# LatarMain.net
KiCad netlist of a schematic drawn in EAGLE
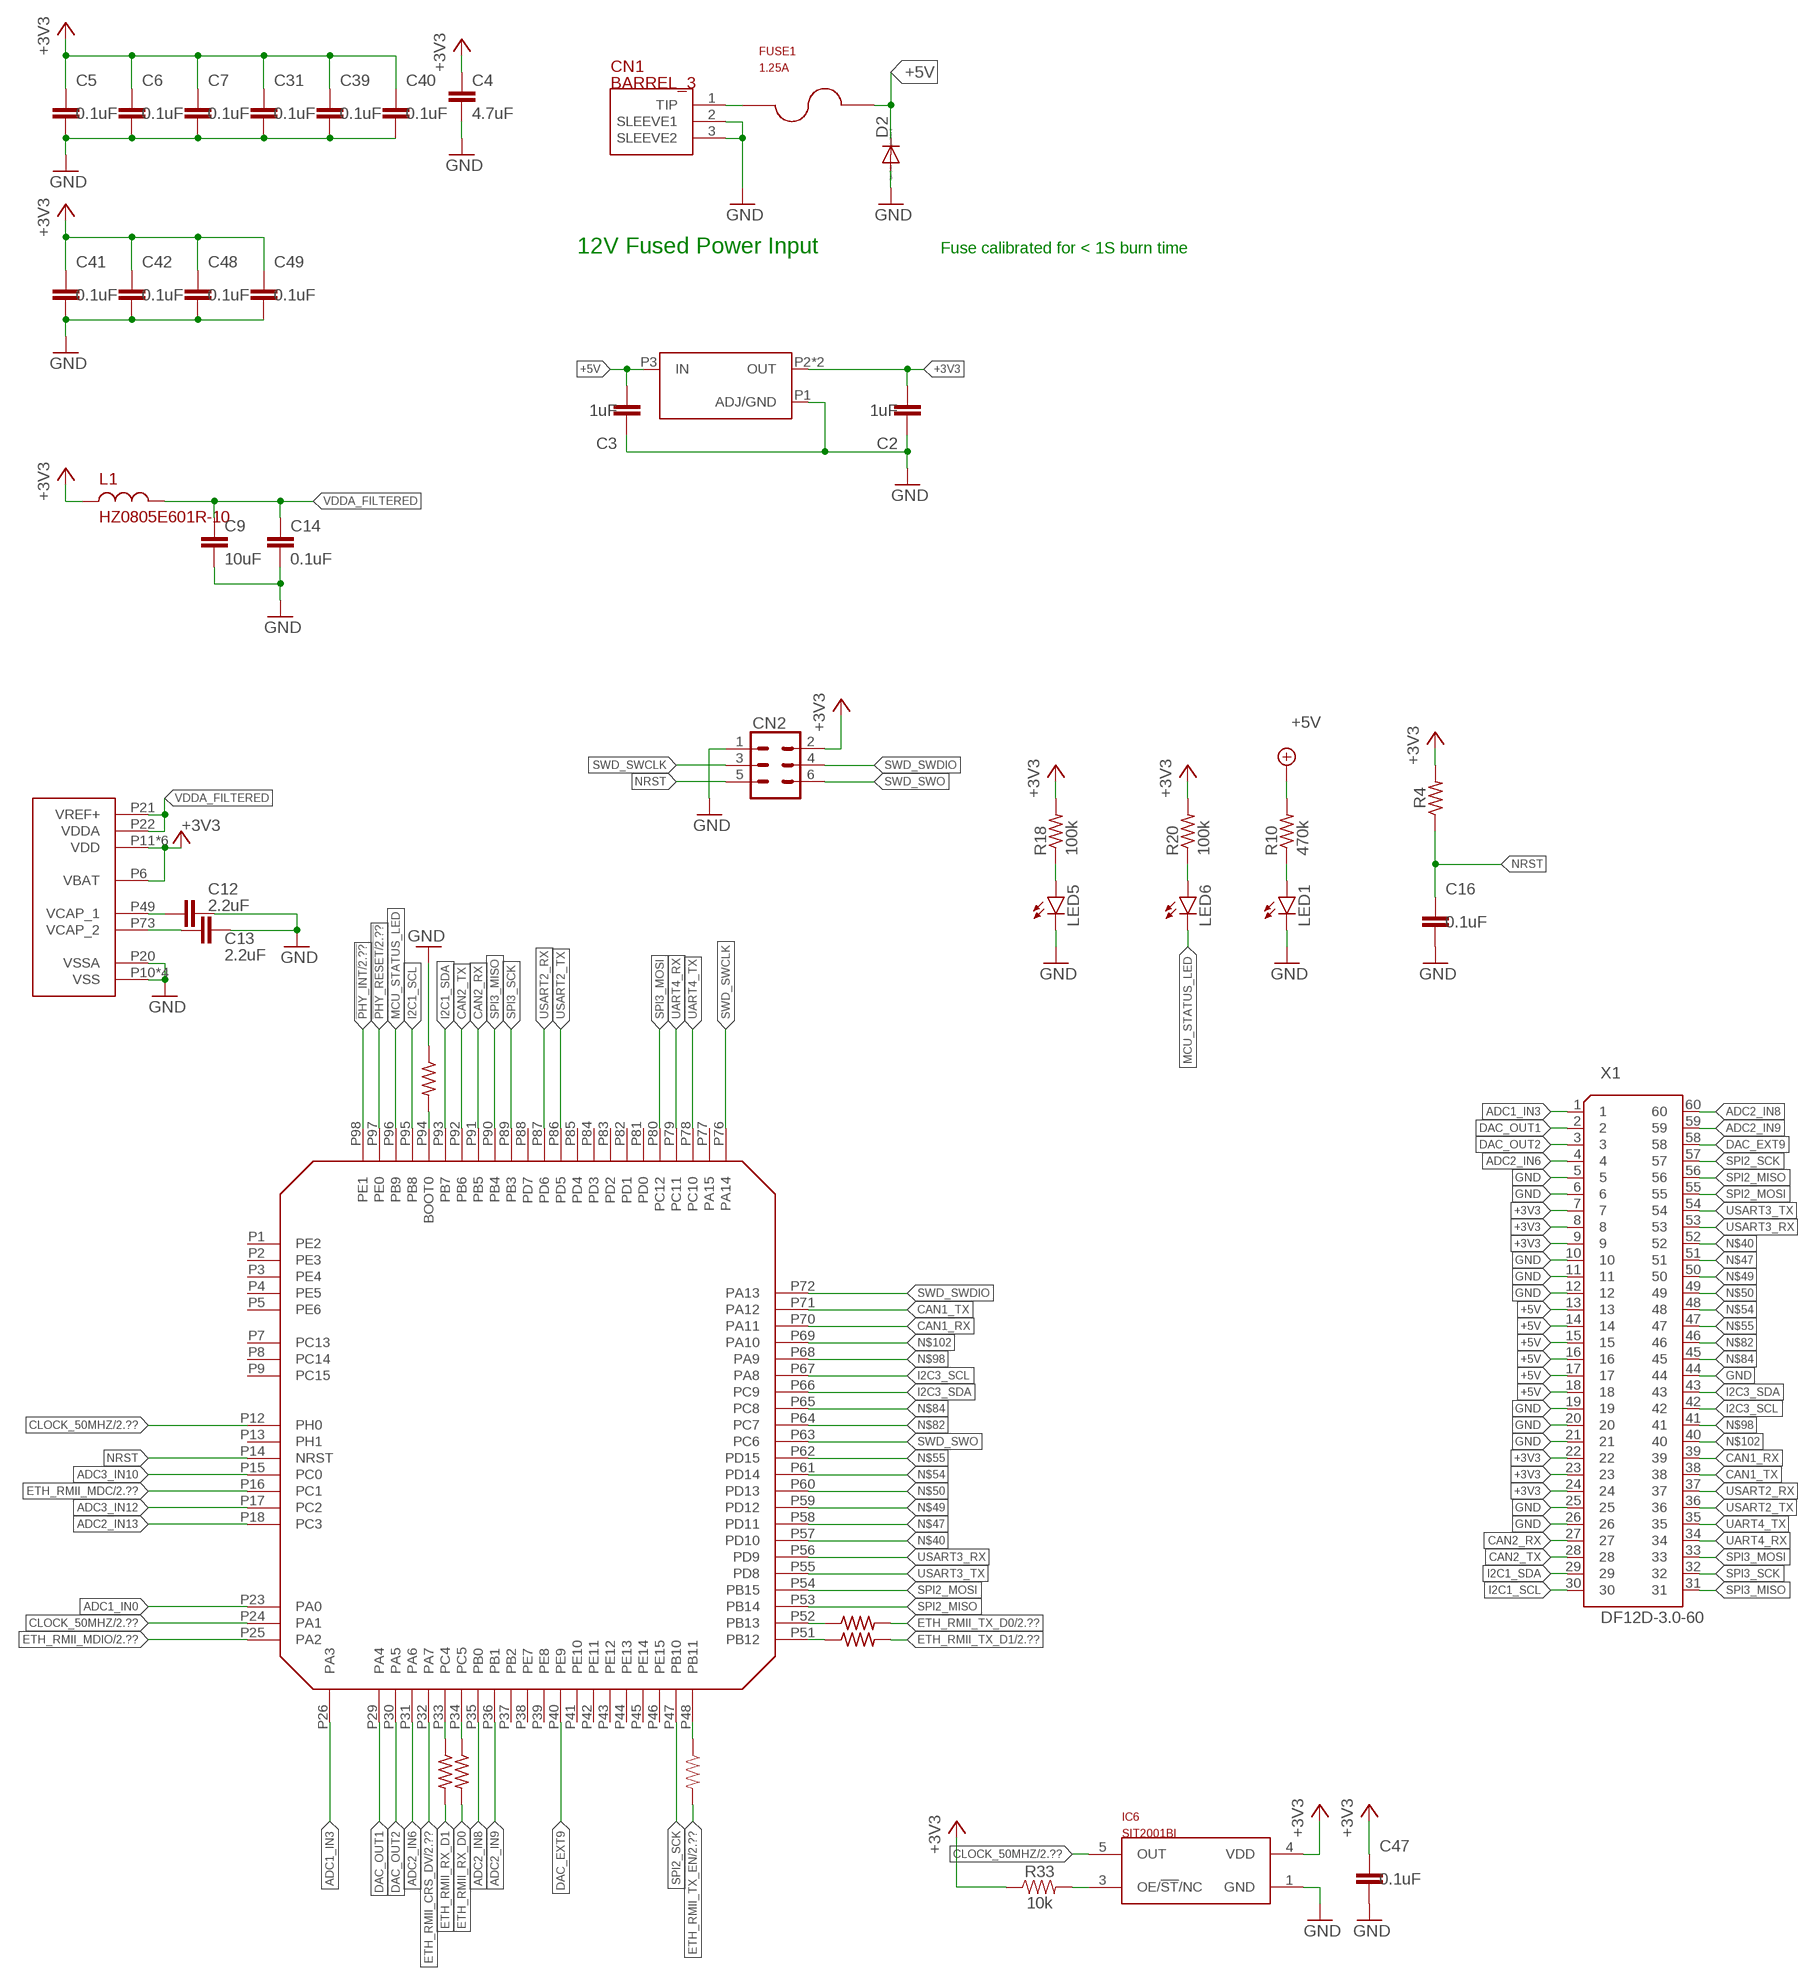
[diagram p0: schematic, sheet 1]
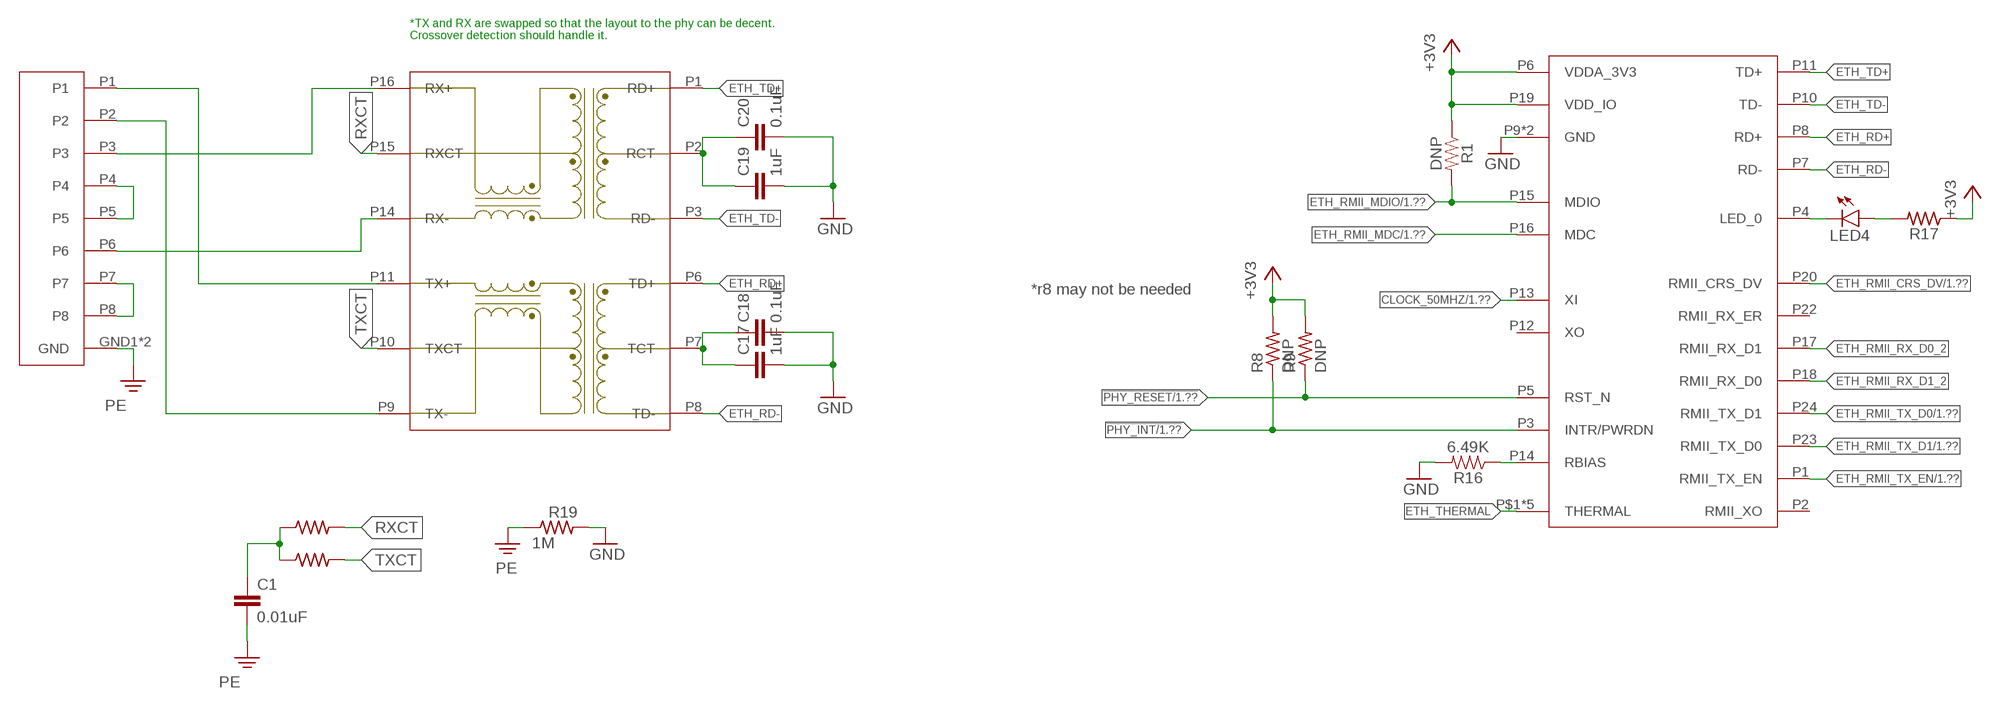
[diagram p1: schematic, sheet 2]

(export (version "E")
  (design (tool "Eeschema 10.0.6"))
  (components
    (comp (ref "C1")
      (value "0.01uF")
      (footprint "eagle-import:C0805")
      (libsource (lib "eagle-import") (part "C-EUC0805"))
    )
    (comp (ref "C17")
      (value "1uF")
      (footprint "eagle-import:C0805")
      (libsource (lib "eagle-import") (part "C-EUC0805"))
    )
    (comp (ref "C18")
      (value "0.1uF")
      (footprint "eagle-import:C0805")
      (libsource (lib "eagle-import") (part "C-EUC0805"))
    )
    (comp (ref "C19")
      (value "1uF")
      (footprint "eagle-import:C0805")
      (libsource (lib "eagle-import") (part "C-EUC0805"))
    )
    (comp (ref "C20")
      (value "0.1uF")
      (footprint "eagle-import:C0805")
      (libsource (lib "eagle-import") (part "C-EUC0805"))
    )
    (comp (ref "LED4")
      (value "LEDCHIP-LED0603")
      (footprint "eagle-import:CHIP-LED0603")
      (libsource (lib "eagle-import") (part "LEDCHIP-LED0603"))
    )
    (comp (ref "R1")
      (value "DNP")
      (footprint "eagle-import:0603")
      (libsource (lib "eagle-import") (part "RESISTOR0603"))
    )
    (comp (ref "R2")
      (value "75R")
      (footprint "eagle-import:R0805")
      (libsource (lib "eagle-import") (part "R-US_R0805"))
    )
    (comp (ref "R5")
      (value "75R")
      (footprint "eagle-import:R0805")
      (libsource (lib "eagle-import") (part "R-US_R0805"))
    )
    (comp (ref "R8")
      (value "DNP")
      (footprint "eagle-import:R0603")
      (libsource (lib "eagle-import") (part "R-US_R0603"))
    )
    (comp (ref "R9")
      (value "DNP")
      (footprint "eagle-import:R0603")
      (libsource (lib "eagle-import") (part "R-US_R0603"))
    )
    (comp (ref "R16")
      (value "6.49K")
      (footprint "eagle-import:0603")
      (libsource (lib "eagle-import") (part "RESISTOR0603"))
    )
    (comp (ref "R17")
      (value "100k")
      (footprint "eagle-import:R0603")
      (libsource (lib "eagle-import") (part "R-US_R0603"))
    )
    (comp (ref "R19")
      (value "1M")
      (footprint "eagle-import:R1206")
      (libsource (lib "eagle-import") (part "R-US_R1206"))
    )
    (comp (ref "U$15")
      (value "749013011")
      (footprint "eagle-import:749013011")
      (libsource (lib "eagle-import") (part "749013011"))
    )
    (comp (ref "U$16")
      (value "A120645-ND")
      (footprint "eagle-import:A120645-ND")
      (libsource (lib "eagle-import") (part "A120645-ND"))
    )
    (comp (ref "U$17")
      (value "DP83825I")
      (footprint "eagle-import:DP83825I")
      (libsource (lib "eagle-import") (part "DP83825I"))
    )
    (comp (ref "C2")
      (value "1uF")
      (footprint "eagle-import:C1206")
      (libsource (lib "eagle-import") (part "C-EUC1206"))
    )
    (comp (ref "C3")
      (value "1uF")
      (footprint "eagle-import:C1206")
      (libsource (lib "eagle-import") (part "C-EUC1206"))
    )
    (comp (ref "C4")
      (value "4.7uF")
      (footprint "eagle-import:C0805")
      (libsource (lib "eagle-import") (part "C-EUC0805"))
    )
    (comp (ref "C5")
      (value "0.1uF")
      (footprint "eagle-import:C0603")
      (libsource (lib "eagle-import") (part "C-EUC0603"))
    )
    (comp (ref "C6")
      (value "0.1uF")
      (footprint "eagle-import:C0603")
      (libsource (lib "eagle-import") (part "C-EUC0603"))
    )
    (comp (ref "C7")
      (value "0.1uF")
      (footprint "eagle-import:C0603")
      (libsource (lib "eagle-import") (part "C-EUC0603"))
    )
    (comp (ref "C9")
      (value "10uF")
      (footprint "eagle-import:C0805")
      (libsource (lib "eagle-import") (part "C-EUC0805"))
    )
    (comp (ref "C12")
      (value "2.2uF")
      (footprint "eagle-import:C0805")
      (libsource (lib "eagle-import") (part "C-EUC0805"))
    )
    (comp (ref "C13")
      (value "2.2uF")
      (footprint "eagle-import:C0805")
      (libsource (lib "eagle-import") (part "C-EUC0805"))
    )
    (comp (ref "C14")
      (value "0.1uF")
      (footprint "eagle-import:C0805")
      (libsource (lib "eagle-import") (part "C-EUC0805"))
    )
    (comp (ref "C16")
      (value "0.1uF")
      (footprint "eagle-import:C0603")
      (libsource (lib "eagle-import") (part "C-EUC0603"))
    )
    (comp (ref "C31")
      (value "0.1uF")
      (footprint "eagle-import:C0603")
      (libsource (lib "eagle-import") (part "C-EUC0603"))
    )
    (comp (ref "C39")
      (value "0.1uF")
      (footprint "eagle-import:C0603")
      (libsource (lib "eagle-import") (part "C-EUC0603"))
    )
    (comp (ref "C40")
      (value "0.1uF")
      (footprint "eagle-import:C0603")
      (libsource (lib "eagle-import") (part "C-EUC0603"))
    )
    (comp (ref "C41")
      (value "0.1uF")
      (footprint "eagle-import:C0603")
      (libsource (lib "eagle-import") (part "C-EUC0603"))
    )
    (comp (ref "C42")
      (value "0.1uF")
      (footprint "eagle-import:C0603")
      (libsource (lib "eagle-import") (part "C-EUC0603"))
    )
    (comp (ref "C47")
      (value "0.1uF")
      (footprint "eagle-import:C0603")
      (libsource (lib "eagle-import") (part "C-EUC0603"))
    )
    (comp (ref "C48")
      (value "0.1uF")
      (footprint "eagle-import:C0603")
      (libsource (lib "eagle-import") (part "C-EUC0603"))
    )
    (comp (ref "C49")
      (value "0.1uF")
      (footprint "eagle-import:C0603")
      (libsource (lib "eagle-import") (part "C-EUC0603"))
    )
    (comp (ref "CN1")
      (value "BARREL_3")
      (footprint "eagle-import:PJ-002AH")
      (libsource (lib "eagle-import") (part "BARREL_3"))
    )
    (comp (ref "CN2")
      (value "CONN_03X22X3_SILK_MALE_PTH")
      (footprint "eagle-import:2X3")
      (libsource (lib "eagle-import") (part "CONN_03X22X3_SILK_MALE_PTH"))
    )
    (comp (ref "D2")
      (value "DIODE-DO214AC")
      (footprint "eagle-import:DO214AC")
      (libsource (lib "eagle-import") (part "DIODE-DO214AC"))
    )
    (comp (ref "FUSE1")
      (value "1.25A")
      (footprint "eagle-import:BEL_FUSE_2SMD")
      (libsource (lib "eagle-import") (part "FUSE"))
    )
    (comp (ref "IC6")
      (value "SIT2001BI")
      (footprint "eagle-import:SOT23-5")
      (libsource (lib "eagle-import") (part "SIT2001BI"))
    )
    (comp (ref "L1")
      (value "HZ0805E601R-10")
      (footprint "eagle-import:R0805")
      (libsource (lib "eagle-import") (part "HZ0805E601R-10"))
    )
    (comp (ref "LED1")
      (value "LEDCHIPLED_0603")
      (footprint "eagle-import:CHIPLED_0603")
      (libsource (lib "eagle-import") (part "LEDCHIPLED_0603"))
    )
    (comp (ref "LED5")
      (value "LEDCHIPLED_0603")
      (footprint "eagle-import:CHIPLED_0603")
      (libsource (lib "eagle-import") (part "LEDCHIPLED_0603"))
    )
    (comp (ref "LED6")
      (value "LEDCHIPLED_0603")
      (footprint "eagle-import:CHIPLED_0603")
      (libsource (lib "eagle-import") (part "LEDCHIPLED_0603"))
    )
    (comp (ref "R4")
      (value "10k")
      (footprint "eagle-import:R0805")
      (libsource (lib "eagle-import") (part "R-US_R0805"))
    )
    (comp (ref "R10")
      (value "470k")
      (footprint "eagle-import:R0603")
      (libsource (lib "eagle-import") (part "R-US_R0603"))
    )
    (comp (ref "R18")
      (value "100k")
      (footprint "eagle-import:R0603")
      (libsource (lib "eagle-import") (part "R-US_R0603"))
    )
    (comp (ref "R20")
      (value "100k")
      (footprint "eagle-import:R0603")
      (libsource (lib "eagle-import") (part "R-US_R0603"))
    )
    (comp (ref "R32")
      (value "50k")
      (footprint "eagle-import:R0402")
      (libsource (lib "eagle-import") (part "R-US_R0402"))
    )
    (comp (ref "R33")
      (value "10k")
      (footprint "eagle-import:0805")
      (libsource (lib "eagle-import") (part "RESISTOR0805"))
    )
    (comp (ref "R34")
      (value "10k")
      (footprint "eagle-import:R0805")
      (libsource (lib "eagle-import") (part "R-US_R0805"))
    )
    (comp (ref "R39")
      (value "50k")
      (footprint "eagle-import:R0402")
      (libsource (lib "eagle-import") (part "R-US_R0402"))
    )
    (comp (ref "R40")
      (value "50k")
      (footprint "eagle-import:R0402")
      (libsource (lib "eagle-import") (part "R-US_R0402"))
    )
    (comp (ref "R41")
      (value "50k")
      (footprint "eagle-import:R0402")
      (libsource (lib "eagle-import") (part "R-US_R0402"))
    )
    (comp (ref "R42")
      (value "50k")
      (footprint "eagle-import:0603")
      (libsource (lib "eagle-import") (part "RESISTOR0603"))
    )
    (comp (ref "U$1")
      (value "AZ1117E")
      (footprint "eagle-import:SOT-223")
      (libsource (lib "eagle-import") (part "AZ1117E"))
    )
    (comp (ref "U$2")
      (value "STM32_F407_LQFP100")
      (footprint "eagle-import:STM32_LQFP100")
      (libsource (lib "eagle-import") (part "STM32_F407_LQFP100"))
    )
    (comp (ref "X1")
      (value "DF12D-3.0-60")
      (footprint "eagle-import:DF12-3.0-60")
      (libsource (lib "eagle-import") (part "DF12D-3.0-60"))
    )
  )
  (nets
    (net (code "1") (name "+3V3") (class "Default")
      (node (ref "C2") (pin "2") (pinfunction "2_2") (pintype "passive"))
      (node (ref "C31") (pin "1") (pinfunction "1_1") (pintype "passive"))
      (node (ref "C39") (pin "1") (pinfunction "1_1") (pintype "passive"))
      (node (ref "C4") (pin "1") (pinfunction "1_1") (pintype "passive"))
      (node (ref "C40") (pin "1") (pinfunction "1_1") (pintype "passive"))
      (node (ref "C41") (pin "1") (pinfunction "1_1") (pintype "passive"))
      (node (ref "C42") (pin "1") (pinfunction "1_1") (pintype "passive"))
      (node (ref "C47") (pin "1") (pinfunction "1_1") (pintype "passive"))
      (node (ref "C48") (pin "1") (pinfunction "1_1") (pintype "passive"))
      (node (ref "C49") (pin "1") (pinfunction "1_1") (pintype "passive"))
      (node (ref "C5") (pin "1") (pinfunction "1_1") (pintype "passive"))
      (node (ref "C6") (pin "1") (pinfunction "1_1") (pintype "passive"))
      (node (ref "C7") (pin "1") (pinfunction "1_1") (pintype "passive"))
      (node (ref "CN2") (pin "2") (pinfunction "2_2") (pintype "bidirectional"))
      (node (ref "IC6") (pin "4") (pinfunction "VDD_4") (pintype "bidirectional"))
      (node (ref "L1") (pin "1") (pinfunction "1_1") (pintype "passive"))
      (node (ref "R1") (pin "1") (pinfunction "1_1") (pintype "passive"))
      (node (ref "R17") (pin "1") (pinfunction "1_1") (pintype "passive"))
      (node (ref "R18") (pin "2") (pinfunction "2_2") (pintype "passive"))
      (node (ref "R20") (pin "2") (pinfunction "2_2") (pintype "passive"))
      (node (ref "R33") (pin "1") (pinfunction "1_1") (pintype "passive"))
      (node (ref "R4") (pin "2") (pinfunction "2_2") (pintype "passive"))
      (node (ref "R8") (pin "2") (pinfunction "2_2") (pintype "passive"))
      (node (ref "R9") (pin "2") (pinfunction "2_2") (pintype "passive"))
      (node (ref "U$1") (pin "P2") (pinfunction "OUT_P2") (pintype "bidirectional"))
      (node (ref "U$1") (pin "TAB") (pinfunction "OUT_TAB") (pintype "bidirectional"))
      (node (ref "U$17") (pin "P19") (pinfunction "VDD_IO_P19") (pintype "bidirectional"))
      (node (ref "U$17") (pin "P6") (pinfunction "VDDA_3V3_P6") (pintype "bidirectional"))
      (node (ref "U$2") (pin "P100") (pinfunction "VDD_P100") (pintype "bidirectional"))
      (node (ref "U$2") (pin "P11") (pinfunction "VDD_P11") (pintype "bidirectional"))
      (node (ref "U$2") (pin "P19") (pinfunction "VDD_P19") (pintype "bidirectional"))
      (node (ref "U$2") (pin "P28") (pinfunction "VDD_P28") (pintype "bidirectional"))
      (node (ref "U$2") (pin "P50") (pinfunction "VDD_P50") (pintype "bidirectional"))
      (node (ref "U$2") (pin "P6") (pinfunction "VBAT_P6") (pintype "bidirectional"))
      (node (ref "U$2") (pin "P75") (pinfunction "VDD_P75") (pintype "bidirectional"))
      (node (ref "X1") (pin "22") (pinfunction "22_22") (pintype "bidirectional"))
      (node (ref "X1") (pin "23") (pinfunction "23_23") (pintype "bidirectional"))
      (node (ref "X1") (pin "24") (pinfunction "24_24") (pintype "bidirectional"))
      (node (ref "X1") (pin "7") (pinfunction "7_7") (pintype "bidirectional"))
      (node (ref "X1") (pin "8") (pinfunction "8_8") (pintype "bidirectional"))
      (node (ref "X1") (pin "9") (pinfunction "9_9") (pintype "bidirectional"))
    )
    (net (code "2") (name "+5V") (class "Default")
      (node (ref "C3") (pin "2") (pinfunction "2_2") (pintype "passive"))
      (node (ref "D2") (pin "C") (pinfunction "C_C") (pintype "passive"))
      (node (ref "FUSE1") (pin "2") (pinfunction "2_2") (pintype "power_in"))
      (node (ref "R10") (pin "2") (pinfunction "2_2") (pintype "passive"))
      (node (ref "U$1") (pin "P3") (pinfunction "IN_P3") (pintype "bidirectional"))
      (node (ref "X1") (pin "13") (pinfunction "13_13") (pintype "bidirectional"))
      (node (ref "X1") (pin "14") (pinfunction "14_14") (pintype "bidirectional"))
      (node (ref "X1") (pin "15") (pinfunction "15_15") (pintype "bidirectional"))
      (node (ref "X1") (pin "16") (pinfunction "16_16") (pintype "bidirectional"))
      (node (ref "X1") (pin "17") (pinfunction "17_17") (pintype "bidirectional"))
      (node (ref "X1") (pin "18") (pinfunction "18_18") (pintype "bidirectional"))
    )
    (net (code "3") (name "ADC1_IN0") (class "Default")
      (node (ref "U$2") (pin "P23") (pinfunction "PA0_P23") (pintype "bidirectional"))
    )
    (net (code "4") (name "ADC1_IN3") (class "Default")
      (node (ref "U$2") (pin "P26") (pinfunction "PA3_P26") (pintype "bidirectional"))
      (node (ref "X1") (pin "1") (pinfunction "1_1") (pintype "bidirectional"))
    )
    (net (code "5") (name "ADC2_IN6") (class "Default")
      (node (ref "U$2") (pin "P31") (pinfunction "PA6_P31") (pintype "bidirectional"))
      (node (ref "X1") (pin "4") (pinfunction "4_4") (pintype "bidirectional"))
    )
    (net (code "6") (name "ADC2_IN8") (class "Default")
      (node (ref "U$2") (pin "P35") (pinfunction "PB0_P35") (pintype "bidirectional"))
      (node (ref "X1") (pin "60") (pinfunction "60_60") (pintype "bidirectional"))
    )
    (net (code "7") (name "ADC2_IN9") (class "Default")
      (node (ref "U$2") (pin "P36") (pinfunction "PB1_P36") (pintype "bidirectional"))
      (node (ref "X1") (pin "59") (pinfunction "59_59") (pintype "bidirectional"))
    )
    (net (code "8") (name "ADC2_IN13") (class "Default")
      (node (ref "U$2") (pin "P18") (pinfunction "PC3_P18") (pintype "bidirectional"))
    )
    (net (code "9") (name "ADC3_IN10") (class "Default")
      (node (ref "U$2") (pin "P15") (pinfunction "PC0_P15") (pintype "bidirectional"))
    )
    (net (code "10") (name "ADC3_IN12") (class "Default")
      (node (ref "U$2") (pin "P17") (pinfunction "PC2_P17") (pintype "bidirectional"))
    )
    (net (code "11") (name "CAN1_RX") (class "Default")
      (node (ref "U$2") (pin "P70") (pinfunction "PA11_P70") (pintype "bidirectional"))
      (node (ref "X1") (pin "39") (pinfunction "39_39") (pintype "bidirectional"))
    )
    (net (code "12") (name "CAN1_TX") (class "Default")
      (node (ref "U$2") (pin "P71") (pinfunction "PA12_P71") (pintype "bidirectional"))
      (node (ref "X1") (pin "38") (pinfunction "38_38") (pintype "bidirectional"))
    )
    (net (code "13") (name "CAN2_RX") (class "Default")
      (node (ref "U$2") (pin "P91") (pinfunction "PB5_P91") (pintype "bidirectional"))
      (node (ref "X1") (pin "27") (pinfunction "27_27") (pintype "bidirectional"))
    )
    (net (code "14") (name "CAN2_TX") (class "Default")
      (node (ref "U$2") (pin "P92") (pinfunction "PB6_P92") (pintype "bidirectional"))
      (node (ref "X1") (pin "28") (pinfunction "28_28") (pintype "bidirectional"))
    )
    (net (code "15") (name "CLOCK_50MHZ") (class "Default")
      (node (ref "IC6") (pin "5") (pinfunction "OUT_5") (pintype "bidirectional"))
      (node (ref "U$17") (pin "P13") (pinfunction "XI_P13") (pintype "bidirectional"))
      (node (ref "U$2") (pin "P12") (pinfunction "PH0_P12") (pintype "bidirectional"))
      (node (ref "U$2") (pin "P24") (pinfunction "PA1_P24") (pintype "bidirectional"))
    )
    (net (code "16") (name "DAC_EXT9") (class "Default")
      (node (ref "U$2") (pin "P40") (pinfunction "PE9_P40") (pintype "bidirectional"))
      (node (ref "X1") (pin "58") (pinfunction "58_58") (pintype "bidirectional"))
    )
    (net (code "17") (name "DAC_OUT1") (class "Default")
      (node (ref "U$2") (pin "P29") (pinfunction "PA4_P29") (pintype "bidirectional"))
      (node (ref "X1") (pin "2") (pinfunction "2_2") (pintype "bidirectional"))
    )
    (net (code "18") (name "DAC_OUT2") (class "Default")
      (node (ref "U$2") (pin "P30") (pinfunction "PA5_P30") (pintype "bidirectional"))
      (node (ref "X1") (pin "3") (pinfunction "3_3") (pintype "bidirectional"))
    )
    (net (code "19") (name "ETH_RD+") (class "Default")
      (node (ref "U$15") (pin "P6") (pinfunction "TD+_P6") (pintype "bidirectional"))
      (node (ref "U$17") (pin "P8") (pinfunction "RD+_P8") (pintype "bidirectional"))
    )
    (net (code "20") (name "ETH_RD-") (class "Default")
      (node (ref "U$15") (pin "P8") (pinfunction "TD-_P8") (pintype "bidirectional"))
      (node (ref "U$17") (pin "P7") (pinfunction "RD-_P7") (pintype "bidirectional"))
    )
    (net (code "21") (name "ETH_RMII_CRS_DV") (class "Default")
      (node (ref "U$17") (pin "P20") (pinfunction "RMII_CRS_DV_P20") (pintype "bidirectional"))
      (node (ref "U$2") (pin "P32") (pinfunction "PA7_P32") (pintype "bidirectional"))
    )
    (net (code "22") (name "ETH_RMII_MDC") (class "Default")
      (node (ref "U$17") (pin "P16") (pinfunction "MDC_P16") (pintype "bidirectional"))
      (node (ref "U$2") (pin "P16") (pinfunction "PC1_P16") (pintype "bidirectional"))
    )
    (net (code "23") (name "ETH_RMII_MDIO") (class "Default")
      (node (ref "R1") (pin "2") (pinfunction "2_2") (pintype "passive"))
      (node (ref "U$17") (pin "P15") (pinfunction "MDIO_P15") (pintype "bidirectional"))
      (node (ref "U$2") (pin "P25") (pinfunction "PA2_P25") (pintype "bidirectional"))
    )
    (net (code "24") (name "ETH_RMII_RX_D0") (class "Default")
      (node (ref "R32") (pin "2") (pinfunction "2_2") (pintype "passive"))
    )
    (net (code "25") (name "ETH_RMII_RX_D0_2") (class "Default")
      (node (ref "U$17") (pin "P17") (pinfunction "RMII_RX_D1_P17") (pintype "bidirectional"))
    )
    (net (code "26") (name "ETH_RMII_RX_D1") (class "Default")
      (node (ref "R39") (pin "2") (pinfunction "2_2") (pintype "passive"))
    )
    (net (code "27") (name "ETH_RMII_RX_D1_2") (class "Default")
      (node (ref "U$17") (pin "P18") (pinfunction "RMII_RX_D0_P18") (pintype "bidirectional"))
    )
    (net (code "28") (name "ETH_RMII_TX_D0") (class "Default")
      (node (ref "R40") (pin "2") (pinfunction "2_2") (pintype "passive"))
      (node (ref "U$17") (pin "P24") (pinfunction "RMII_TX_D1_P24") (pintype "bidirectional"))
    )
    (net (code "29") (name "ETH_RMII_TX_D1") (class "Default")
      (node (ref "R41") (pin "2") (pinfunction "2_2") (pintype "passive"))
      (node (ref "U$17") (pin "P23") (pinfunction "RMII_TX_D0_P23") (pintype "bidirectional"))
    )
    (net (code "30") (name "ETH_RMII_TX_EN") (class "Default")
      (node (ref "R42") (pin "2") (pinfunction "2_2") (pintype "passive"))
      (node (ref "U$17") (pin "P1") (pinfunction "RMII_TX_EN_P1") (pintype "bidirectional"))
    )
    (net (code "31") (name "ETH_TD+") (class "Default")
      (node (ref "U$15") (pin "P1") (pinfunction "RD+_P1") (pintype "bidirectional"))
      (node (ref "U$17") (pin "P11") (pinfunction "TD+_P11") (pintype "bidirectional"))
    )
    (net (code "32") (name "ETH_TD-") (class "Default")
      (node (ref "U$15") (pin "P3") (pinfunction "RD-_P3") (pintype "bidirectional"))
      (node (ref "U$17") (pin "P10") (pinfunction "TD-_P10") (pintype "bidirectional"))
    )
    (net (code "33") (name "ETH_THERMAL") (class "Default")
      (node (ref "U$17") (pin "P$1") (pinfunction "THERMAL_P$1") (pintype "bidirectional"))
      (node (ref "U$17") (pin "P$2") (pinfunction "THERMAL_P$2") (pintype "bidirectional"))
      (node (ref "U$17") (pin "P$3") (pinfunction "THERMAL_P$3") (pintype "bidirectional"))
      (node (ref "U$17") (pin "P$4") (pinfunction "THERMAL_P$4") (pintype "bidirectional"))
      (node (ref "U$17") (pin "PT") (pinfunction "THERMAL_PT") (pintype "bidirectional"))
    )
    (net (code "34") (name "GND") (class "Default")
      (node (ref "C12") (pin "2") (pinfunction "2_2") (pintype "passive"))
      (node (ref "C13") (pin "2") (pinfunction "2_2") (pintype "passive"))
      (node (ref "C14") (pin "2") (pinfunction "2_2") (pintype "passive"))
      (node (ref "C16") (pin "2") (pinfunction "2_2") (pintype "passive"))
      (node (ref "C17") (pin "2") (pinfunction "2_2") (pintype "passive"))
      (node (ref "C18") (pin "2") (pinfunction "2_2") (pintype "passive"))
      (node (ref "C19") (pin "2") (pinfunction "2_2") (pintype "passive"))
      (node (ref "C2") (pin "1") (pinfunction "1_1") (pintype "passive"))
      (node (ref "C20") (pin "2") (pinfunction "2_2") (pintype "passive"))
      (node (ref "C3") (pin "1") (pinfunction "1_1") (pintype "passive"))
      (node (ref "C31") (pin "2") (pinfunction "2_2") (pintype "passive"))
      (node (ref "C39") (pin "2") (pinfunction "2_2") (pintype "passive"))
      (node (ref "C4") (pin "2") (pinfunction "2_2") (pintype "passive"))
      (node (ref "C40") (pin "2") (pinfunction "2_2") (pintype "passive"))
      (node (ref "C41") (pin "2") (pinfunction "2_2") (pintype "passive"))
      (node (ref "C42") (pin "2") (pinfunction "2_2") (pintype "passive"))
      (node (ref "C47") (pin "2") (pinfunction "2_2") (pintype "passive"))
      (node (ref "C48") (pin "2") (pinfunction "2_2") (pintype "passive"))
      (node (ref "C49") (pin "2") (pinfunction "2_2") (pintype "passive"))
      (node (ref "C5") (pin "2") (pinfunction "2_2") (pintype "passive"))
      (node (ref "C6") (pin "2") (pinfunction "2_2") (pintype "passive"))
      (node (ref "C7") (pin "2") (pinfunction "2_2") (pintype "passive"))
      (node (ref "C9") (pin "2") (pinfunction "2_2") (pintype "passive"))
      (node (ref "CN1") (pin "2") (pinfunction "SLEEVE1_2") (pintype "bidirectional"))
      (node (ref "CN1") (pin "3") (pinfunction "SLEEVE2_3") (pintype "bidirectional"))
      (node (ref "CN2") (pin "1") (pinfunction "1_1") (pintype "bidirectional"))
      (node (ref "D2") (pin "A") (pinfunction "A_A") (pintype "passive"))
      (node (ref "IC6") (pin "1") (pinfunction "GND_1") (pintype "bidirectional"))
      (node (ref "LED1") (pin "C") (pinfunction "C_C") (pintype "passive"))
      (node (ref "LED5") (pin "C") (pinfunction "C_C") (pintype "passive"))
      (node (ref "R16") (pin "2") (pinfunction "2_2") (pintype "passive"))
      (node (ref "R19") (pin "2") (pinfunction "2_2") (pintype "passive"))
      (node (ref "R34") (pin "1") (pinfunction "1_1") (pintype "passive"))
      (node (ref "U$1") (pin "P1") (pinfunction "ADJ/GND_P1") (pintype "bidirectional"))
      (node (ref "U$17") (pin "P21") (pinfunction "GND_P21") (pintype "bidirectional"))
      (node (ref "U$17") (pin "P9") (pinfunction "GND_P9") (pintype "bidirectional"))
      (node (ref "U$2") (pin "P10") (pinfunction "VSS_P10") (pintype "bidirectional"))
      (node (ref "U$2") (pin "P20") (pinfunction "VSSA_P20") (pintype "bidirectional"))
      (node (ref "U$2") (pin "P27") (pinfunction "VSS_P27") (pintype "bidirectional"))
      (node (ref "U$2") (pin "P74") (pinfunction "VSS_P74") (pintype "bidirectional"))
      (node (ref "U$2") (pin "P99") (pinfunction "VSS_P99") (pintype "bidirectional"))
      (node (ref "X1") (pin "10") (pinfunction "10_10") (pintype "bidirectional"))
      (node (ref "X1") (pin "11") (pinfunction "11_11") (pintype "bidirectional"))
      (node (ref "X1") (pin "12") (pinfunction "12_12") (pintype "bidirectional"))
      (node (ref "X1") (pin "19") (pinfunction "19_19") (pintype "bidirectional"))
      (node (ref "X1") (pin "20") (pinfunction "20_20") (pintype "bidirectional"))
      (node (ref "X1") (pin "21") (pinfunction "21_21") (pintype "bidirectional"))
      (node (ref "X1") (pin "25") (pinfunction "25_25") (pintype "bidirectional"))
      (node (ref "X1") (pin "26") (pinfunction "26_26") (pintype "bidirectional"))
      (node (ref "X1") (pin "44") (pinfunction "44_44") (pintype "bidirectional"))
      (node (ref "X1") (pin "5") (pinfunction "5_5") (pintype "bidirectional"))
      (node (ref "X1") (pin "6") (pinfunction "6_6") (pintype "bidirectional"))
    )
    (net (code "35") (name "I2C1_SCL") (class "Default")
      (node (ref "U$2") (pin "P95") (pinfunction "PB8_P95") (pintype "bidirectional"))
      (node (ref "X1") (pin "30") (pinfunction "30_30") (pintype "bidirectional"))
    )
    (net (code "36") (name "I2C1_SDA") (class "Default")
      (node (ref "U$2") (pin "P93") (pinfunction "PB7_P93") (pintype "bidirectional"))
      (node (ref "X1") (pin "29") (pinfunction "29_29") (pintype "bidirectional"))
    )
    (net (code "37") (name "I2C3_SCL") (class "Default")
      (node (ref "U$2") (pin "P67") (pinfunction "PA8_P67") (pintype "bidirectional"))
      (node (ref "X1") (pin "42") (pinfunction "42_42") (pintype "bidirectional"))
    )
    (net (code "38") (name "I2C3_SDA") (class "Default")
      (node (ref "U$2") (pin "P66") (pinfunction "PC9_P66") (pintype "bidirectional"))
      (node (ref "X1") (pin "43") (pinfunction "43_43") (pintype "bidirectional"))
    )
    (net (code "39") (name "MCU_STATUS_LED") (class "Default")
      (node (ref "LED6") (pin "C") (pinfunction "C_C") (pintype "passive"))
      (node (ref "U$2") (pin "P96") (pinfunction "PB9_P96") (pintype "bidirectional"))
    )
    (net (code "40") (name "N$40") (class "Default")
      (node (ref "U$2") (pin "P57") (pinfunction "PD10_P57") (pintype "bidirectional"))
      (node (ref "X1") (pin "52") (pinfunction "52_52") (pintype "bidirectional"))
    )
    (net (code "41") (name "N$47") (class "Default")
      (node (ref "U$2") (pin "P58") (pinfunction "PD11_P58") (pintype "bidirectional"))
      (node (ref "X1") (pin "51") (pinfunction "51_51") (pintype "bidirectional"))
    )
    (net (code "42") (name "N$49") (class "Default")
      (node (ref "U$2") (pin "P59") (pinfunction "PD12_P59") (pintype "bidirectional"))
      (node (ref "X1") (pin "50") (pinfunction "50_50") (pintype "bidirectional"))
    )
    (net (code "43") (name "N$50") (class "Default")
      (node (ref "U$2") (pin "P60") (pinfunction "PD13_P60") (pintype "bidirectional"))
      (node (ref "X1") (pin "49") (pinfunction "49_49") (pintype "bidirectional"))
    )
    (net (code "44") (name "N$54") (class "Default")
      (node (ref "U$2") (pin "P61") (pinfunction "PD14_P61") (pintype "bidirectional"))
      (node (ref "X1") (pin "48") (pinfunction "48_48") (pintype "bidirectional"))
    )
    (net (code "45") (name "N$55") (class "Default")
      (node (ref "U$2") (pin "P62") (pinfunction "PD15_P62") (pintype "bidirectional"))
      (node (ref "X1") (pin "47") (pinfunction "47_47") (pintype "bidirectional"))
    )
    (net (code "46") (name "N$82") (class "Default")
      (node (ref "U$2") (pin "P64") (pinfunction "PC7_P64") (pintype "bidirectional"))
      (node (ref "X1") (pin "46") (pinfunction "46_46") (pintype "bidirectional"))
    )
    (net (code "47") (name "N$84") (class "Default")
      (node (ref "U$2") (pin "P65") (pinfunction "PC8_P65") (pintype "bidirectional"))
      (node (ref "X1") (pin "45") (pinfunction "45_45") (pintype "bidirectional"))
    )
    (net (code "48") (name "N$98") (class "Default")
      (node (ref "U$2") (pin "P68") (pinfunction "PA9_P68") (pintype "bidirectional"))
      (node (ref "X1") (pin "41") (pinfunction "41_41") (pintype "bidirectional"))
    )
    (net (code "49") (name "N$102") (class "Default")
      (node (ref "U$2") (pin "P69") (pinfunction "PA10_P69") (pintype "bidirectional"))
      (node (ref "X1") (pin "40") (pinfunction "40_40") (pintype "bidirectional"))
    )
    (net (code "50") (name "NRST") (class "Default")
      (node (ref "C16") (pin "1") (pinfunction "1_1") (pintype "passive"))
      (node (ref "CN2") (pin "5") (pinfunction "5_5") (pintype "bidirectional"))
      (node (ref "R4") (pin "1") (pinfunction "1_1") (pintype "passive"))
      (node (ref "U$2") (pin "P14") (pinfunction "NRST_P14") (pintype "bidirectional"))
    )
    (net (code "51") (name "Net-(C1-Pad1)") (class "Default")
      (node (ref "C1") (pin "1") (pinfunction "1_1") (pintype "passive"))
      (node (ref "R2") (pin "1") (pinfunction "1_1") (pintype "passive"))
      (node (ref "R5") (pin "1") (pinfunction "1_1") (pintype "passive"))
    )
    (net (code "52") (name "Net-(CN1-TIP)") (class "Default")
      (node (ref "CN1") (pin "1") (pinfunction "TIP_1") (pintype "bidirectional"))
      (node (ref "FUSE1") (pin "1") (pinfunction "1_1") (pintype "power_in"))
    )
    (net (code "53") (name "Net-(IC6-OE{slash}~{ST}{slash}NC)") (class "Default")
      (node (ref "IC6") (pin "3") (pinfunction "OE/~{ST}/NC_3") (pintype "bidirectional"))
      (node (ref "R33") (pin "2") (pinfunction "2_2") (pintype "passive"))
    )
    (net (code "54") (name "Net-(LED1-PadA)") (class "Default")
      (node (ref "LED1") (pin "A") (pinfunction "A_A") (pintype "passive"))
      (node (ref "R10") (pin "1") (pinfunction "1_1") (pintype "passive"))
    )
    (net (code "55") (name "Net-(LED4-PadA)") (class "Default")
      (node (ref "LED4") (pin "A") (pinfunction "A_A") (pintype "passive"))
      (node (ref "R17") (pin "2") (pinfunction "2_2") (pintype "passive"))
    )
    (net (code "56") (name "Net-(LED5-PadA)") (class "Default")
      (node (ref "LED5") (pin "A") (pinfunction "A_A") (pintype "passive"))
      (node (ref "R18") (pin "1") (pinfunction "1_1") (pintype "passive"))
    )
    (net (code "57") (name "Net-(LED6-PadA)") (class "Default")
      (node (ref "LED6") (pin "A") (pinfunction "A_A") (pintype "passive"))
      (node (ref "R20") (pin "1") (pinfunction "1_1") (pintype "passive"))
    )
    (net (code "58") (name "Net-(U$2-BOOT0)") (class "Default")
      (node (ref "R34") (pin "2") (pinfunction "2_2") (pintype "passive"))
      (node (ref "U$2") (pin "P94") (pinfunction "BOOT0_P94") (pintype "bidirectional"))
    )
    (net (code "59") (name "Net-(U$2-PB11)") (class "Default")
      (node (ref "R42") (pin "1") (pinfunction "1_1") (pintype "passive"))
      (node (ref "U$2") (pin "P48") (pinfunction "PB11_P48") (pintype "bidirectional"))
    )
    (net (code "60") (name "Net-(U$2-PB12)") (class "Default")
      (node (ref "R41") (pin "1") (pinfunction "1_1") (pintype "passive"))
      (node (ref "U$2") (pin "P51") (pinfunction "PB12_P51") (pintype "bidirectional"))
    )
    (net (code "61") (name "Net-(U$2-PB13)") (class "Default")
      (node (ref "R40") (pin "1") (pinfunction "1_1") (pintype "passive"))
      (node (ref "U$2") (pin "P52") (pinfunction "PB13_P52") (pintype "bidirectional"))
    )
    (net (code "62") (name "Net-(U$2-PC4)") (class "Default")
      (node (ref "R39") (pin "1") (pinfunction "1_1") (pintype "passive"))
      (node (ref "U$2") (pin "P33") (pinfunction "PC4_P33") (pintype "bidirectional"))
    )
    (net (code "63") (name "Net-(U$2-PC5)") (class "Default")
      (node (ref "R32") (pin "1") (pinfunction "1_1") (pintype "passive"))
      (node (ref "U$2") (pin "P34") (pinfunction "PC5_P34") (pintype "bidirectional"))
    )
    (net (code "64") (name "Net-(U$2-VCAP_1)") (class "Default")
      (node (ref "C12") (pin "1") (pinfunction "1_1") (pintype "passive"))
      (node (ref "U$2") (pin "P49") (pinfunction "VCAP_1_P49") (pintype "bidirectional"))
    )
    (net (code "65") (name "Net-(U$2-VCAP_2)") (class "Default")
      (node (ref "C13") (pin "1") (pinfunction "1_1") (pintype "passive"))
      (node (ref "U$2") (pin "P73") (pinfunction "VCAP_2_P73") (pintype "bidirectional"))
    )
    (net (code "66") (name "Net-(U$15-RCT)") (class "Default")
      (node (ref "C19") (pin "1") (pinfunction "1_1") (pintype "passive"))
      (node (ref "C20") (pin "1") (pinfunction "1_1") (pintype "passive"))
      (node (ref "U$15") (pin "P2") (pinfunction "RCT_P2") (pintype "bidirectional"))
    )
    (net (code "67") (name "Net-(U$15-RX+)") (class "Default")
      (node (ref "U$15") (pin "P16") (pinfunction "RX+_P16") (pintype "bidirectional"))
      (node (ref "U$16") (pin "P3") (pinfunction "P3_P3") (pintype "bidirectional"))
    )
    (net (code "68") (name "Net-(U$15-RX-)") (class "Default")
      (node (ref "U$15") (pin "P14") (pinfunction "RX-_P14") (pintype "bidirectional"))
      (node (ref "U$16") (pin "P6") (pinfunction "P6_P6") (pintype "bidirectional"))
    )
    (net (code "69") (name "Net-(U$15-TCT)") (class "Default")
      (node (ref "C17") (pin "1") (pinfunction "1_1") (pintype "passive"))
      (node (ref "C18") (pin "1") (pinfunction "1_1") (pintype "passive"))
      (node (ref "U$15") (pin "P7") (pinfunction "TCT_P7") (pintype "bidirectional"))
    )
    (net (code "70") (name "Net-(U$15-TX+)") (class "Default")
      (node (ref "U$15") (pin "P11") (pinfunction "TX+_P11") (pintype "bidirectional"))
      (node (ref "U$16") (pin "P1") (pinfunction "P1_P1") (pintype "bidirectional"))
    )
    (net (code "71") (name "Net-(U$15-TX-)") (class "Default")
      (node (ref "U$15") (pin "P9") (pinfunction "TX-_P9") (pintype "bidirectional"))
      (node (ref "U$16") (pin "P2") (pinfunction "P2_P2") (pintype "bidirectional"))
    )
    (net (code "72") (name "Net-(U$16-PadP4)") (class "Default")
      (node (ref "U$16") (pin "P4") (pinfunction "P4_P4") (pintype "bidirectional"))
      (node (ref "U$16") (pin "P5") (pinfunction "P5_P5") (pintype "bidirectional"))
    )
    (net (code "73") (name "Net-(U$16-PadP7)") (class "Default")
      (node (ref "U$16") (pin "P7") (pinfunction "P7_P7") (pintype "bidirectional"))
      (node (ref "U$16") (pin "P8") (pinfunction "P8_P8") (pintype "bidirectional"))
    )
    (net (code "74") (name "Net-(U$17-LED_0)") (class "Default")
      (node (ref "LED4") (pin "C") (pinfunction "C_C") (pintype "passive"))
      (node (ref "U$17") (pin "P4") (pinfunction "LED_0_P4") (pintype "bidirectional"))
    )
    (net (code "75") (name "Net-(U$17-RBIAS)") (class "Default")
      (node (ref "R16") (pin "1") (pinfunction "1_1") (pintype "passive"))
      (node (ref "U$17") (pin "P14") (pinfunction "RBIAS_P14") (pintype "bidirectional"))
    )
    (net (code "76") (name "PE") (class "Default")
      (node (ref "C1") (pin "2") (pinfunction "2_2") (pintype "passive"))
      (node (ref "R19") (pin "1") (pinfunction "1_1") (pintype "passive"))
      (node (ref "U$16") (pin "GND1") (pinfunction "GND_GND1") (pintype "bidirectional"))
      (node (ref "U$16") (pin "GND2") (pinfunction "GND_GND2") (pintype "bidirectional"))
    )
    (net (code "77") (name "RXCT") (class "Default")
      (node (ref "R2") (pin "2") (pinfunction "2_2") (pintype "passive"))
      (node (ref "U$15") (pin "P15") (pinfunction "RXCT_P15") (pintype "bidirectional"))
    )
    (net (code "78") (name "SPI2_MISO") (class "Default")
      (node (ref "U$2") (pin "P53") (pinfunction "PB14_P53") (pintype "bidirectional"))
      (node (ref "X1") (pin "56") (pinfunction "56_56") (pintype "bidirectional"))
    )
    (net (code "79") (name "SPI2_MOSI") (class "Default")
      (node (ref "U$2") (pin "P54") (pinfunction "PB15_P54") (pintype "bidirectional"))
      (node (ref "X1") (pin "55") (pinfunction "55_55") (pintype "bidirectional"))
    )
    (net (code "80") (name "SPI2_SCK") (class "Default")
      (node (ref "U$2") (pin "P47") (pinfunction "PB10_P47") (pintype "bidirectional"))
      (node (ref "X1") (pin "57") (pinfunction "57_57") (pintype "bidirectional"))
    )
    (net (code "81") (name "SPI3_MISO") (class "Default")
      (node (ref "U$2") (pin "P90") (pinfunction "PB4_P90") (pintype "bidirectional"))
      (node (ref "X1") (pin "31") (pinfunction "31_31") (pintype "bidirectional"))
    )
    (net (code "82") (name "SPI3_MOSI") (class "Default")
      (node (ref "U$2") (pin "P80") (pinfunction "PC12_P80") (pintype "bidirectional"))
      (node (ref "X1") (pin "33") (pinfunction "33_33") (pintype "bidirectional"))
    )
    (net (code "83") (name "SPI3_SCK") (class "Default")
      (node (ref "U$2") (pin "P89") (pinfunction "PB3_P89") (pintype "bidirectional"))
      (node (ref "X1") (pin "32") (pinfunction "32_32") (pintype "bidirectional"))
    )
    (net (code "84") (name "SWD_SWCLK") (class "Default")
      (node (ref "CN2") (pin "3") (pinfunction "3_3") (pintype "bidirectional"))
      (node (ref "U$2") (pin "P76") (pinfunction "PA14_P76") (pintype "bidirectional"))
    )
    (net (code "85") (name "SWD_SWDIO") (class "Default")
      (node (ref "CN2") (pin "4") (pinfunction "4_4") (pintype "bidirectional"))
      (node (ref "U$2") (pin "P72") (pinfunction "PA13_P72") (pintype "bidirectional"))
    )
    (net (code "86") (name "SWD_SWO") (class "Default")
      (node (ref "CN2") (pin "6") (pinfunction "6_6") (pintype "bidirectional"))
      (node (ref "U$2") (pin "P63") (pinfunction "PC6_P63") (pintype "bidirectional"))
    )
    (net (code "87") (name "TXCT") (class "Default")
      (node (ref "R5") (pin "2") (pinfunction "2_2") (pintype "passive"))
      (node (ref "U$15") (pin "P10") (pinfunction "TXCT_P10") (pintype "bidirectional"))
    )
    (net (code "88") (name "UART4_RX") (class "Default")
      (node (ref "U$2") (pin "P79") (pinfunction "PC11_P79") (pintype "bidirectional"))
      (node (ref "X1") (pin "34") (pinfunction "34_34") (pintype "bidirectional"))
    )
    (net (code "89") (name "UART4_TX") (class "Default")
      (node (ref "U$2") (pin "P78") (pinfunction "PC10_P78") (pintype "bidirectional"))
      (node (ref "X1") (pin "35") (pinfunction "35_35") (pintype "bidirectional"))
    )
    (net (code "90") (name "USART2_RX") (class "Default")
      (node (ref "U$2") (pin "P87") (pinfunction "PD6_P87") (pintype "bidirectional"))
      (node (ref "X1") (pin "37") (pinfunction "37_37") (pintype "bidirectional"))
    )
    (net (code "91") (name "USART2_TX") (class "Default")
      (node (ref "U$2") (pin "P86") (pinfunction "PD5_P86") (pintype "bidirectional"))
      (node (ref "X1") (pin "36") (pinfunction "36_36") (pintype "bidirectional"))
    )
    (net (code "92") (name "USART3_RX") (class "Default")
      (node (ref "U$2") (pin "P56") (pinfunction "PD9_P56") (pintype "bidirectional"))
      (node (ref "X1") (pin "53") (pinfunction "53_53") (pintype "bidirectional"))
    )
    (net (code "93") (name "USART3_TX") (class "Default")
      (node (ref "U$2") (pin "P55") (pinfunction "PD8_P55") (pintype "bidirectional"))
      (node (ref "X1") (pin "54") (pinfunction "54_54") (pintype "bidirectional"))
    )
    (net (code "94") (name "VDDA_FILTERED") (class "Default")
      (node (ref "C14") (pin "1") (pinfunction "1_1") (pintype "passive"))
      (node (ref "C9") (pin "1") (pinfunction "1_1") (pintype "passive"))
      (node (ref "L1") (pin "2") (pinfunction "2_2") (pintype "passive"))
      (node (ref "U$2") (pin "P21") (pinfunction "VREF+_P21") (pintype "bidirectional"))
      (node (ref "U$2") (pin "P22") (pinfunction "VDDA_P22") (pintype "bidirectional"))
    )
    (net (code "95") (name "unconnected-(U$2-PA15-PadP77)") (class "Default")
      (node (ref "U$2") (pin "P77") (pinfunction "PA15_P77") (pintype "bidirectional"))
    )
    (net (code "96") (name "unconnected-(U$2-PB2-PadP37)") (class "Default")
      (node (ref "U$2") (pin "P37") (pinfunction "PB2_P37") (pintype "bidirectional"))
    )
    (net (code "97") (name "unconnected-(U$2-PC13-PadP7)") (class "Default")
      (node (ref "U$2") (pin "P7") (pinfunction "PC13_P7") (pintype "bidirectional"))
    )
    (net (code "98") (name "unconnected-(U$2-PC14-PadP8)") (class "Default")
      (node (ref "U$2") (pin "P8") (pinfunction "PC14_P8") (pintype "bidirectional"))
    )
    (net (code "99") (name "unconnected-(U$2-PC15-PadP9)") (class "Default")
      (node (ref "U$2") (pin "P9") (pinfunction "PC15_P9") (pintype "bidirectional"))
    )
    (net (code "100") (name "unconnected-(U$2-PD0-PadP81)") (class "Default")
      (node (ref "U$2") (pin "P81") (pinfunction "PD0_P81") (pintype "bidirectional"))
    )
    (net (code "101") (name "unconnected-(U$2-PD1-PadP82)") (class "Default")
      (node (ref "U$2") (pin "P82") (pinfunction "PD1_P82") (pintype "bidirectional"))
    )
    (net (code "102") (name "unconnected-(U$2-PD2-PadP83)") (class "Default")
      (node (ref "U$2") (pin "P83") (pinfunction "PD2_P83") (pintype "bidirectional"))
    )
    (net (code "103") (name "unconnected-(U$2-PD3-PadP84)") (class "Default")
      (node (ref "U$2") (pin "P84") (pinfunction "PD3_P84") (pintype "bidirectional"))
    )
    (net (code "104") (name "unconnected-(U$2-PD4-PadP85)") (class "Default")
      (node (ref "U$2") (pin "P85") (pinfunction "PD4_P85") (pintype "bidirectional"))
    )
    (net (code "105") (name "unconnected-(U$2-PD7-PadP88)") (class "Default")
      (node (ref "U$2") (pin "P88") (pinfunction "PD7_P88") (pintype "bidirectional"))
    )
    (net (code "106") (name "unconnected-(U$2-PE2-PadP1)") (class "Default")
      (node (ref "U$2") (pin "P1") (pinfunction "PE2_P1") (pintype "bidirectional"))
    )
    (net (code "107") (name "unconnected-(U$2-PE3-PadP2)") (class "Default")
      (node (ref "U$2") (pin "P2") (pinfunction "PE3_P2") (pintype "bidirectional"))
    )
    (net (code "108") (name "unconnected-(U$2-PE4-PadP3)") (class "Default")
      (node (ref "U$2") (pin "P3") (pinfunction "PE4_P3") (pintype "bidirectional"))
    )
    (net (code "109") (name "unconnected-(U$2-PE5-PadP4)") (class "Default")
      (node (ref "U$2") (pin "P4") (pinfunction "PE5_P4") (pintype "bidirectional"))
    )
    (net (code "110") (name "unconnected-(U$2-PE6-PadP5)") (class "Default")
      (node (ref "U$2") (pin "P5") (pinfunction "PE6_P5") (pintype "bidirectional"))
    )
    (net (code "111") (name "unconnected-(U$2-PE7-PadP38)") (class "Default")
      (node (ref "U$2") (pin "P38") (pinfunction "PE7_P38") (pintype "bidirectional"))
    )
    (net (code "112") (name "unconnected-(U$2-PE8-PadP39)") (class "Default")
      (node (ref "U$2") (pin "P39") (pinfunction "PE8_P39") (pintype "bidirectional"))
    )
    (net (code "113") (name "unconnected-(U$2-PE10-PadP41)") (class "Default")
      (node (ref "U$2") (pin "P41") (pinfunction "PE10_P41") (pintype "bidirectional"))
    )
    (net (code "114") (name "unconnected-(U$2-PE11-PadP42)") (class "Default")
      (node (ref "U$2") (pin "P42") (pinfunction "PE11_P42") (pintype "bidirectional"))
    )
    (net (code "115") (name "unconnected-(U$2-PE12-PadP43)") (class "Default")
      (node (ref "U$2") (pin "P43") (pinfunction "PE12_P43") (pintype "bidirectional"))
    )
    (net (code "116") (name "unconnected-(U$2-PE13-PadP44)") (class "Default")
      (node (ref "U$2") (pin "P44") (pinfunction "PE13_P44") (pintype "bidirectional"))
    )
    (net (code "117") (name "unconnected-(U$2-PE14-PadP45)") (class "Default")
      (node (ref "U$2") (pin "P45") (pinfunction "PE14_P45") (pintype "bidirectional"))
    )
    (net (code "118") (name "unconnected-(U$2-PE15-PadP46)") (class "Default")
      (node (ref "U$2") (pin "P46") (pinfunction "PE15_P46") (pintype "bidirectional"))
    )
    (net (code "119") (name "unconnected-(U$2-PH1-PadP13)") (class "Default")
      (node (ref "U$2") (pin "P13") (pinfunction "PH1_P13") (pintype "bidirectional"))
    )
    (net (code "120") (name "unconnected-(U$17-RMII_RX_ER-PadP22)") (class "Default")
      (node (ref "U$17") (pin "P22") (pinfunction "RMII_RX_ER_P22") (pintype "bidirectional"))
    )
    (net (code "121") (name "unconnected-(U$17-RMII_XO-PadP2)") (class "Default")
      (node (ref "U$17") (pin "P2") (pinfunction "RMII_XO_P2") (pintype "bidirectional"))
    )
    (net (code "122") (name "unconnected-(U$17-XO-PadP12)") (class "Default")
      (node (ref "U$17") (pin "P12") (pinfunction "XO_P12") (pintype "bidirectional"))
    )
    (net (code "123") (name "~{PHY_INT}") (class "Default")
      (node (ref "R8") (pin "1") (pinfunction "1_1") (pintype "passive"))
      (node (ref "U$17") (pin "P3") (pinfunction "INTR/PWRDN_P3") (pintype "bidirectional"))
      (node (ref "U$2") (pin "P98") (pinfunction "PE1_P98") (pintype "bidirectional"))
    )
    (net (code "124") (name "~{PHY_RESET}") (class "Default")
      (node (ref "R9") (pin "1") (pinfunction "1_1") (pintype "passive"))
      (node (ref "U$17") (pin "P5") (pinfunction "RST_N_P5") (pintype "bidirectional"))
      (node (ref "U$2") (pin "P97") (pinfunction "PE0_P97") (pintype "bidirectional"))
    )
  )
)
